# CH32V407WEU-R0.net
KiCad netlist of a schematic drawn in Altium Designer
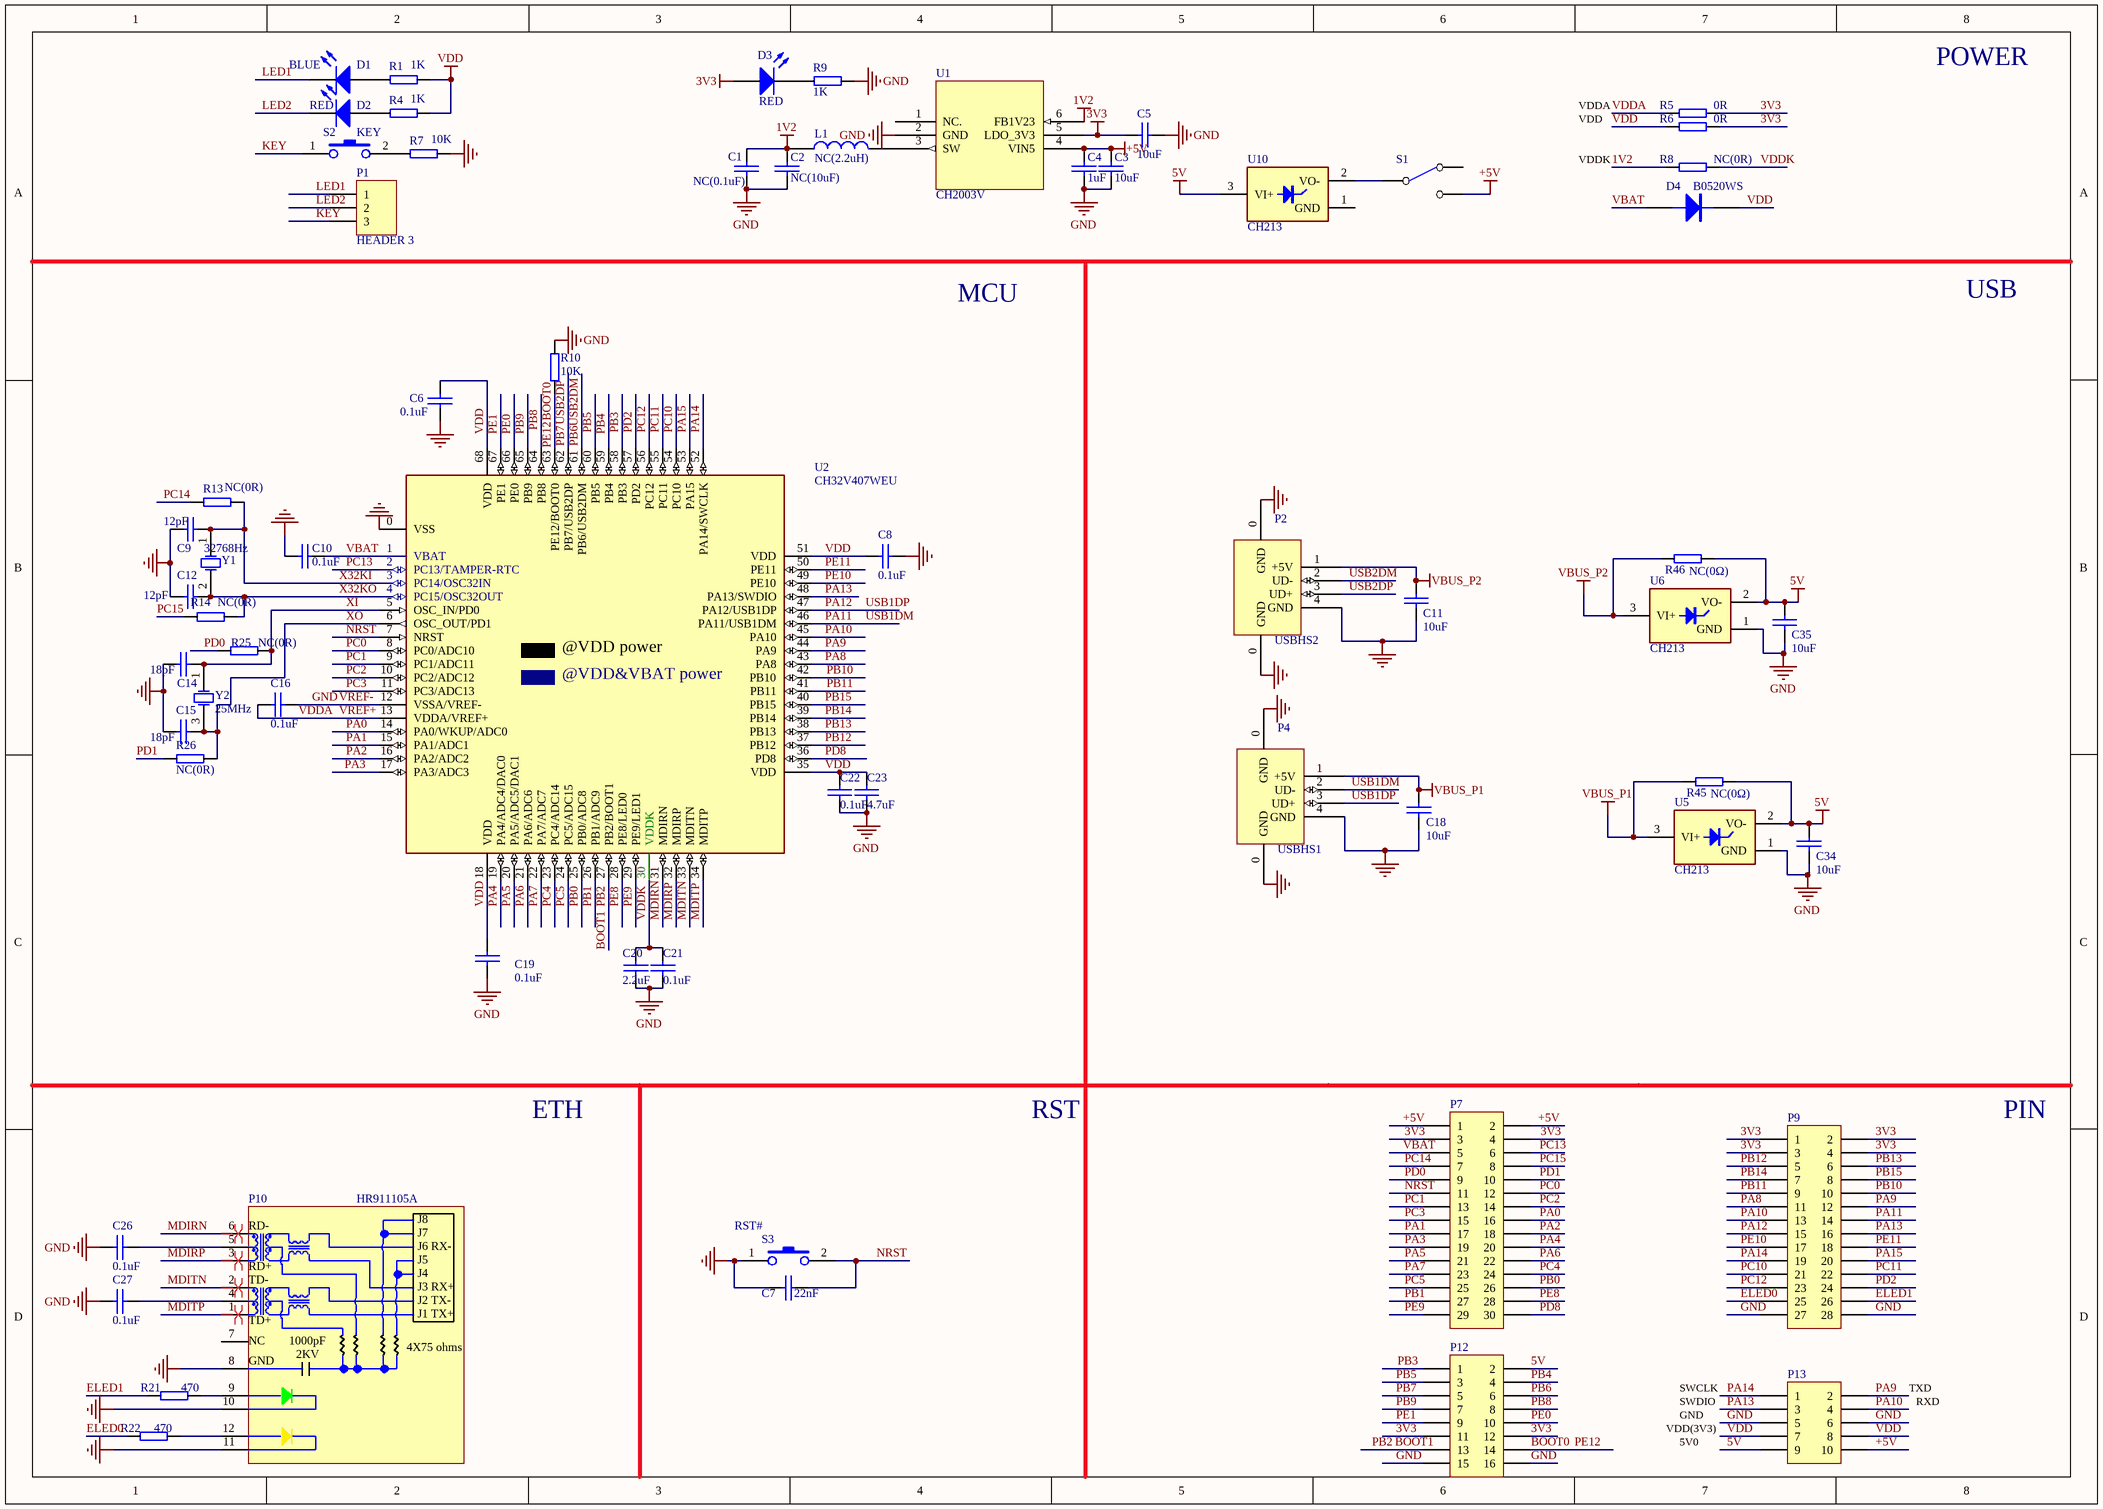
[diagram p0: CH32V407WEU-R0.SchDoc]

(export (version "E")
  (design (tool "Eeschema 10.0.6"))
  (components
    (comp (ref "C1")
      (value "NC(0.1uF)")
      (footprint "0402_C")
      (description "Capacitor")
      (libsource (lib "") (part "CAP_1"))
    )
    (comp (ref "C2")
      (value "NC(10uF)")
      (footprint "0603_C")
      (description "Capacitor")
      (libsource (lib "*") (part "CAP"))
    )
    (comp (ref "C3")
      (value "10uF")
      (footprint "0603_C")
      (description "Capacitor")
      (libsource (lib "*") (part "CAP"))
    )
    (comp (ref "C4")
      (value "1uF")
      (footprint "0402_C")
      (description "Capacitor")
      (libsource (lib "") (part "CAP_1"))
    )
    (comp (ref "C5")
      (value "10uF")
      (footprint "0603_C")
      (description "Capacitor")
      (libsource (lib "*") (part "CAP"))
    )
    (comp (ref "C6")
      (value "0.1uF")
      (footprint "0402_C")
      (description "Capacitor")
      (libsource (lib "*") (part "CAP"))
    )
    (comp (ref "C7")
      (value "22nF")
      (footprint "0402_C")
      (description "Capacitor")
      (libsource (lib "") (part "CAP_2"))
    )
    (comp (ref "C8")
      (value "0.1uF")
      (footprint "0402_C")
      (description "Capacitor")
      (libsource (lib "*") (part "CAP"))
    )
    (comp (ref "C9")
      (value "12pF")
      (footprint "0402_C")
      (description "Capacitor")
      (libsource (lib "*") (part "CAP"))
    )
    (comp (ref "C10")
      (value "0.1uF")
      (footprint "0402_C")
      (description "Capacitor")
      (libsource (lib "*") (part "CAP"))
    )
    (comp (ref "C11")
      (value "10uF")
      (footprint "0603_C")
      (description "Capacitor")
      (libsource (lib "") (part "CAP_2"))
    )
    (comp (ref "C12")
      (value "12pF")
      (footprint "0402_C")
      (description "Capacitor")
      (libsource (lib "*") (part "CAP"))
    )
    (comp (ref "C14")
      (value "18pF")
      (footprint "0402_C")
      (description "Capacitor")
      (libsource (lib "*") (part "CAP"))
    )
    (comp (ref "C15")
      (value "18pF")
      (footprint "0402_C")
      (description "Capacitor")
      (libsource (lib "*") (part "CAP"))
    )
    (comp (ref "C16")
      (value "0.1uF")
      (footprint "0402_C")
      (description "Capacitor")
      (libsource (lib "*") (part "CAP"))
    )
    (comp (ref "C18")
      (value "10uF")
      (footprint "0603_C")
      (description "Capacitor")
      (libsource (lib "") (part "CAP_2"))
    )
    (comp (ref "C19")
      (value "0.1uF")
      (footprint "0402_C")
      (description "Capacitor")
      (libsource (lib "*") (part "CAP"))
    )
    (comp (ref "C20")
      (value "2.2uF")
      (footprint "0402_C")
      (description "Capacitor")
      (libsource (lib "*") (part "CAP"))
    )
    (comp (ref "C21")
      (value "0.1uF")
      (footprint "0402_C")
      (description "Capacitor")
      (libsource (lib "*") (part "CAP"))
    )
    (comp (ref "C22")
      (value "0.1uF")
      (footprint "0402_C")
      (description "Capacitor")
      (libsource (lib "*") (part "CAP"))
    )
    (comp (ref "C23")
      (value "4.7uF")
      (footprint "0402_C")
      (description "Capacitor")
      (libsource (lib "*") (part "CAP"))
    )
    (comp (ref "C26")
      (value "0.1uF")
      (footprint "0402_C")
      (description "Capacitor")
      (libsource (lib "wch_sch_others") (part "CAP"))
    )
    (comp (ref "C27")
      (value "0.1uF")
      (footprint "0402_C")
      (description "Capacitor")
      (libsource (lib "wch_sch_others") (part "CAP"))
    )
    (comp (ref "C34")
      (value "10uF")
      (footprint "0603_C")
      (description "Capacitor")
      (libsource (lib "") (part "CAP_2"))
    )
    (comp (ref "C35")
      (value "10uF")
      (footprint "0603_C")
      (description "Capacitor")
      (libsource (lib "") (part "CAP_2"))
    )
    (comp (ref "D1")
      (value "BLUE")
      (footprint "0603+")
      (description "Typical INFRARED GaAs LED")
      (fields (field (name "PUBLISHER") "Altium Limited"))
      (libsource (lib "*") (part "LED0"))
    )
    (comp (ref "D2")
      (value "RED")
      (footprint "0603+")
      (description "Typical INFRARED GaAs LED")
      (fields (field (name "PUBLISHER") "Altium Limited"))
      (libsource (lib "*") (part "LED0"))
    )
    (comp (ref "D3")
      (value "RED")
      (footprint "0603+")
      (description "Typical INFRARED GaAs LED")
      (fields (field (name "PUBLISHER") "Altium Limited"))
      (libsource (lib "*") (part "LED0"))
    )
    (comp (ref "D4")
      (value "B0520WS")
      (footprint "SOD-323")
      (description "Diode")
      (libsource (lib "*") (part "DIODE"))
    )
    (comp (ref "L1") (value "NC(2.2uH)") (footprint "CD32") (libsource (lib "*") (part "INDUCTOR")))
    (comp (ref "P1")
      (value "HEADER 3")
      (footprint "SIP3-2.54MM")
      (description "Header, 3-Pin")
      (libsource (lib "wch_sch_others") (part "HEADER 3"))
    )
    (comp (ref "P2")
      (value "USBHS2")
      (footprint "USBAF")
      (description "USB Port")
      (libsource (lib "*") (part "USB"))
    )
    (comp (ref "P4")
      (value "USBHS1")
      (footprint "USBAF")
      (description "USB Port")
      (libsource (lib "*") (part "USB"))
    )
    (comp (ref "P7")
      (value "HEADER 15x2")
      (footprint "MYPCB:IDC30-2.54MM")
      (description "Header, 15-Pin, Dual row")
      (libsource (lib "wch_sch_others") (part "HEADER 15x2"))
    )
    (comp (ref "P9")
      (value "HEADER 14x2")
      (footprint "MYPCB:IDC28-2.54MM")
      (description "Header, 14-Pin, Dual row")
      (libsource (lib "wch_sch_others") (part "HEADER 14x2"))
    )
    (comp (ref "P10") (value "HR911105A") (footprint "HR911105A") (libsource (lib "*") (part "HR911105A")))
    (comp (ref "P12")
      (value "Ppin")
      (footprint "IDC16-2.54mm")
      (description "Header, 8-Pin, Dual row, Right Angle")
      (fields (field (name "PUBLISHER") "Altium Limited"))
      (libsource (lib "Miscellaneous Connectors") (part "Header 8X2H"))
    )
    (comp (ref "P13")
      (value "LINK")
      (footprint "IDC10-2.54mm")
      (description "Header, 5-Pin, Dual row, Right Angle")
      (fields (field (name "PUBLISHER") "Altium Limited"))
      (libsource (lib "Miscellaneous Connectors") (part "Header 5X2H"))
    )
    (comp (ref "R1") (value "1K") (footprint "0402") (libsource (lib "wch_sch_others") (part "RES")))
    (comp (ref "R4") (value "1K") (footprint "0402") (libsource (lib "wch_sch_others") (part "RES")))
    (comp (ref "R5") (value "0R") (footprint "0402") (libsource (lib "*") (part "R")))
    (comp (ref "R6") (value "0R") (footprint "0402") (libsource (lib "*") (part "R")))
    (comp (ref "R7") (value "10K") (footprint "0402") (libsource (lib "wch_sch_others") (part "RES")))
    (comp (ref "R8") (value "NC(0R)") (footprint "0402") (libsource (lib "*") (part "R")))
    (comp (ref "R9") (value "1K") (footprint "0402") (libsource (lib "wch_sch_others") (part "RES")))
    (comp (ref "R10") (value "10K") (footprint "0402") (libsource (lib "wch_sch_others") (part "RES")))
    (comp (ref "R13") (value "NC(0R)") (footprint "0402") (libsource (lib "wch_sch_others") (part "RES")))
    (comp (ref "R14") (value "NC(0R)") (footprint "0402") (libsource (lib "wch_sch_others") (part "RES")))
    (comp (ref "R21") (value "470") (footprint "0402") (libsource (lib "wch_sch_others") (part "RES")))
    (comp (ref "R22") (value "470") (footprint "0402") (libsource (lib "wch_sch_others") (part "RES")))
    (comp (ref "R25") (value "NC(0R)") (footprint "0402") (libsource (lib "wch_sch_others") (part "RES")))
    (comp (ref "R26") (value "NC(0R)") (footprint "0402") (libsource (lib "wch_sch_others") (part "RES")))
    (comp (ref "R45") (value "NC(0Ω)") (footprint "0402") (libsource (lib "wch_sch_others") (part "RES")))
    (comp (ref "R46") (value "NC(0Ω)") (footprint "0402") (libsource (lib "wch_sch_others") (part "RES")))
    (comp (ref "S1") (value "SW SPDT") (footprint "SW1") (libsource (lib "*") (part "SW SPDT")))
    (comp (ref "S2")
      (value "KEY")
      (footprint "SMD_6.1x3.65x2.5mm-KEY")
      (libsource (lib "wch_sch_others") (part "KEY1"))
    )
    (comp (ref "S3")
      (value "RST#")
      (footprint "SMD_6.1x3.65x2.5mm-KEY")
      (libsource (lib "wch_sch_others") (part "KEY1"))
    )
    (comp (ref "U1")
      (value "CH2003V")
      (footprint "SOT-23-6")
      (description "Step-Down DC-DC Converter, 5V input, 1.23V * 800mA output, with LDO 3.3V * 200mA")
      (libsource (lib "CHXXX") (part "CH2003V"))
    )
    (comp (ref "U2")
      (value "CH32V407WEU")
      (footprint "QFN68_8X8")
      (description "RISC-V FPU HD-MCU, 175MHz, USB_480M, 100M Ethernet & Phy, CAN, ADC, DAC")
      (libsource (lib "CHXXX") (part "CH32V407WEU"))
    )
    (comp (ref "U5")
      (value "CH213")
      (footprint "SOT-23-3")
      (description "Ideal Diode 5V*1A")
      (libsource (lib "CHXXX") (part "CH213E"))
    )
    (comp (ref "U6")
      (value "CH213")
      (footprint "SOT-23-3")
      (description "Ideal Diode 5V*1A")
      (libsource (lib "CHXXX") (part "CH213E"))
    )
    (comp (ref "U10")
      (value "CH213")
      (footprint "SOT-23-3")
      (description "Ideal Diode 5V*1A")
      (libsource (lib "CHXXX") (part "CH213E"))
    )
    (comp (ref "Y1")
      (value "32768Hz")
      (footprint "FC-135")
      (description "Crystal Oscillator")
      (fields (field (name "PUBLISHER") "Altium Limited"))
      (libsource (lib "*") (part "XTAL"))
    )
    (comp (ref "Y2")
      (value "25MHz")
      (footprint "XT3225")
      (description "Crystal Oscillator")
      (fields (field (name "PUBLISHER") "Altium Limited"))
      (libsource (lib "") (part "XTAL_1"))
    )
  )
  (nets
    (net (code "1") (name "+5V") (class "Default")
      (node (ref "C3") (pin "2") (pinfunction "2_2") (pintype "passive"))
      (node (ref "C4") (pin "2") (pinfunction "2_2") (pintype "passive"))
      (node (ref "P13") (pin "10") (pinfunction "10_10") (pintype "passive"))
      (node (ref "P7") (pin "1") (pinfunction "1_1") (pintype "passive"))
      (node (ref "P7") (pin "2") (pinfunction "2_2") (pintype "passive"))
      (node (ref "S1") (pin "2") (pinfunction "NC_2") (pintype "passive"))
      (node (ref "U1") (pin "4") (pinfunction "VIN5_4") (pintype "power_in"))
    )
    (net (code "3") (name "/BOOT0") (class "Default")
      (node (ref "P12") (pin "14") (pinfunction "14_14") (pintype "passive"))
      (node (ref "R10") (pin "2") (pintype "passive"))
      (node (ref "U2") (pin "63") (pinfunction "PE12/BOOT0_63") (pintype "bidirectional"))
    )
    (net (code "4") (name "/BOOT1") (class "Default")
      (node (ref "P12") (pin "13") (pinfunction "13_13") (pintype "passive"))
      (node (ref "U2") (pin "27") (pinfunction "PB2/BOOT1_27") (pintype "bidirectional"))
    )
    (net (code "5") (name "/ELED0") (class "Default")
      (node (ref "P9") (pin "25") (pinfunction "25_25") (pintype "passive"))
      (node (ref "R22") (pin "1") (pintype "passive"))
    )
    (net (code "6") (name "/ELED1") (class "Default")
      (node (ref "P9") (pin "26") (pinfunction "26_26") (pintype "passive"))
      (node (ref "R21") (pin "1") (pintype "passive"))
    )
    (net (code "7") (name "/KEY") (class "Default")
      (node (ref "P1") (pin "3") (pinfunction "3_3") (pintype "passive"))
      (node (ref "S2") (pin "1") (pinfunction "1_1") (pintype "passive"))
    )
    (net (code "8") (name "/LED1") (class "Default")
      (node (ref "D1") (pin "2") (pinfunction "K_2") (pintype "passive"))
      (node (ref "P1") (pin "1") (pinfunction "1_1") (pintype "passive"))
    )
    (net (code "9") (name "/LED2") (class "Default")
      (node (ref "D2") (pin "2") (pinfunction "K_2") (pintype "passive"))
      (node (ref "P1") (pin "2") (pinfunction "2_2") (pintype "passive"))
    )
    (net (code "10") (name "/MDIRN") (class "Default")
      (node (ref "P10") (pin "6") (pintype "passive"))
      (node (ref "U2") (pin "31") (pinfunction "MDIRN_31") (pintype "bidirectional"))
    )
    (net (code "11") (name "/MDIRP") (class "Default")
      (node (ref "P10") (pin "3") (pintype "passive"))
      (node (ref "U2") (pin "32") (pinfunction "MDIRP_32") (pintype "bidirectional"))
    )
    (net (code "12") (name "/MDITN") (class "Default")
      (node (ref "P10") (pin "2") (pintype "passive"))
      (node (ref "U2") (pin "33") (pinfunction "MDITN_33") (pintype "bidirectional"))
    )
    (net (code "13") (name "/MDITP") (class "Default")
      (node (ref "P10") (pin "1") (pintype "passive"))
      (node (ref "U2") (pin "34") (pinfunction "MDITP_34") (pintype "bidirectional"))
    )
    (net (code "14") (name "/NRST") (class "Default")
      (node (ref "C7") (pin "2") (pinfunction "2_2") (pintype "passive"))
      (node (ref "P7") (pin "11") (pinfunction "11_11") (pintype "passive"))
      (node (ref "S3") (pin "2") (pinfunction "2_2") (pintype "passive"))
      (node (ref "U2") (pin "7") (pinfunction "NRST_7") (pintype "input"))
    )
    (net (code "15") (name "/PA0") (class "Default")
      (node (ref "P7") (pin "16") (pinfunction "16_16") (pintype "passive"))
      (node (ref "U2") (pin "14") (pinfunction "PA0/WKUP/ADC0_14") (pintype "bidirectional"))
    )
    (net (code "16") (name "/PA1") (class "Default")
      (node (ref "P7") (pin "17") (pinfunction "17_17") (pintype "passive"))
      (node (ref "U2") (pin "15") (pinfunction "PA1/ADC1_15") (pintype "bidirectional"))
    )
    (net (code "17") (name "/PA2") (class "Default")
      (node (ref "P7") (pin "18") (pinfunction "18_18") (pintype "passive"))
      (node (ref "U2") (pin "16") (pinfunction "PA2/ADC2_16") (pintype "bidirectional"))
    )
    (net (code "18") (name "/PA3") (class "Default")
      (node (ref "P7") (pin "19") (pinfunction "19_19") (pintype "passive"))
      (node (ref "U2") (pin "17") (pinfunction "PA3/ADC3_17") (pintype "bidirectional"))
    )
    (net (code "19") (name "/PA4") (class "Default")
      (node (ref "P7") (pin "20") (pinfunction "20_20") (pintype "passive"))
      (node (ref "U2") (pin "19") (pinfunction "PA4/ADC4/DAC0_19") (pintype "bidirectional"))
    )
    (net (code "20") (name "/PA5") (class "Default")
      (node (ref "P7") (pin "21") (pinfunction "21_21") (pintype "passive"))
      (node (ref "U2") (pin "20") (pinfunction "PA5/ADC5/DAC1_20") (pintype "bidirectional"))
    )
    (net (code "21") (name "/PA6") (class "Default")
      (node (ref "P7") (pin "22") (pinfunction "22_22") (pintype "passive"))
      (node (ref "U2") (pin "21") (pinfunction "PA6/ADC6_21") (pintype "bidirectional"))
    )
    (net (code "22") (name "/PA7") (class "Default")
      (node (ref "P7") (pin "23") (pinfunction "23_23") (pintype "passive"))
      (node (ref "U2") (pin "22") (pinfunction "PA7/ADC7_22") (pintype "bidirectional"))
    )
    (net (code "23") (name "/PA8") (class "Default")
      (node (ref "P9") (pin "11") (pinfunction "11_11") (pintype "passive"))
      (node (ref "U2") (pin "43") (pinfunction "PA8_43") (pintype "bidirectional"))
    )
    (net (code "24") (name "/PA9") (class "Default")
      (node (ref "P13") (pin "2") (pinfunction "2_2") (pintype "passive"))
      (node (ref "P9") (pin "12") (pinfunction "12_12") (pintype "passive"))
      (node (ref "U2") (pin "44") (pinfunction "PA9_44") (pintype "bidirectional"))
    )
    (net (code "25") (name "/PA10") (class "Default")
      (node (ref "P13") (pin "4") (pinfunction "4_4") (pintype "passive"))
      (node (ref "P9") (pin "13") (pinfunction "13_13") (pintype "passive"))
      (node (ref "U2") (pin "45") (pinfunction "PA10_45") (pintype "bidirectional"))
    )
    (net (code "26") (name "/PA11") (class "Default")
      (node (ref "P4") (pin "2") (pinfunction "UD-_2") (pintype "bidirectional"))
      (node (ref "P9") (pin "14") (pinfunction "14_14") (pintype "passive"))
      (node (ref "U2") (pin "46") (pinfunction "PA11/USB1DM_46") (pintype "bidirectional"))
    )
    (net (code "27") (name "/PA12") (class "Default")
      (node (ref "P4") (pin "3") (pinfunction "UD+_3") (pintype "bidirectional"))
      (node (ref "P9") (pin "15") (pinfunction "15_15") (pintype "passive"))
      (node (ref "U2") (pin "47") (pinfunction "PA12/USB1DP_47") (pintype "bidirectional"))
    )
    (net (code "28") (name "/PA13") (class "Default")
      (node (ref "P13") (pin "3") (pinfunction "3_3") (pintype "passive"))
      (node (ref "P9") (pin "16") (pinfunction "16_16") (pintype "passive"))
      (node (ref "U2") (pin "48") (pinfunction "PA13/SWDIO_48") (pintype "bidirectional"))
    )
    (net (code "29") (name "/PA14") (class "Default")
      (node (ref "P13") (pin "1") (pinfunction "1_1") (pintype "passive"))
      (node (ref "P9") (pin "19") (pinfunction "19_19") (pintype "passive"))
      (node (ref "U2") (pin "52") (pinfunction "PA14/SWCLK_52") (pintype "bidirectional"))
    )
    (net (code "30") (name "/PA15") (class "Default")
      (node (ref "P9") (pin "20") (pinfunction "20_20") (pintype "passive"))
      (node (ref "U2") (pin "53") (pinfunction "PA15_53") (pintype "bidirectional"))
    )
    (net (code "31") (name "/PB0") (class "Default")
      (node (ref "P7") (pin "26") (pinfunction "26_26") (pintype "passive"))
      (node (ref "U2") (pin "25") (pinfunction "PB0/ADC8_25") (pintype "bidirectional"))
    )
    (net (code "32") (name "/PB1") (class "Default")
      (node (ref "P7") (pin "27") (pinfunction "27_27") (pintype "passive"))
      (node (ref "U2") (pin "26") (pinfunction "PB1/ADC9_26") (pintype "bidirectional"))
    )
    (net (code "33") (name "/PB3") (class "Default")
      (node (ref "P12") (pin "1") (pinfunction "1_1") (pintype "passive"))
      (node (ref "U2") (pin "58") (pinfunction "PB3_58") (pintype "bidirectional"))
    )
    (net (code "34") (name "/PB4") (class "Default")
      (node (ref "P12") (pin "4") (pinfunction "4_4") (pintype "passive"))
      (node (ref "U2") (pin "59") (pinfunction "PB4_59") (pintype "bidirectional"))
    )
    (net (code "35") (name "/PB5") (class "Default")
      (node (ref "P12") (pin "3") (pinfunction "3_3") (pintype "passive"))
      (node (ref "U2") (pin "60") (pinfunction "PB5_60") (pintype "bidirectional"))
    )
    (net (code "36") (name "/PB6") (class "Default")
      (node (ref "P12") (pin "6") (pinfunction "6_6") (pintype "passive"))
      (node (ref "P2") (pin "2") (pinfunction "UD-_2") (pintype "bidirectional"))
      (node (ref "U2") (pin "61") (pinfunction "PB6/USB2DM_61") (pintype "bidirectional"))
    )
    (net (code "37") (name "/PB7") (class "Default")
      (node (ref "P12") (pin "5") (pinfunction "5_5") (pintype "passive"))
      (node (ref "P2") (pin "3") (pinfunction "UD+_3") (pintype "bidirectional"))
      (node (ref "U2") (pin "62") (pinfunction "PB7/USB2DP_62") (pintype "bidirectional"))
    )
    (net (code "38") (name "/PB8") (class "Default")
      (node (ref "P12") (pin "8") (pinfunction "8_8") (pintype "passive"))
      (node (ref "U2") (pin "64") (pinfunction "PB8_64") (pintype "bidirectional"))
    )
    (net (code "39") (name "/PB9") (class "Default")
      (node (ref "P12") (pin "7") (pinfunction "7_7") (pintype "passive"))
      (node (ref "U2") (pin "65") (pinfunction "PB9_65") (pintype "bidirectional"))
    )
    (net (code "40") (name "/PB10") (class "Default")
      (node (ref "P9") (pin "10") (pinfunction "10_10") (pintype "passive"))
      (node (ref "U2") (pin "42") (pinfunction "PB10_42") (pintype "bidirectional"))
    )
    (net (code "41") (name "/PB11") (class "Default")
      (node (ref "P9") (pin "9") (pinfunction "9_9") (pintype "passive"))
      (node (ref "U2") (pin "41") (pinfunction "PB11_41") (pintype "bidirectional"))
    )
    (net (code "42") (name "/PB12") (class "Default")
      (node (ref "P9") (pin "5") (pinfunction "5_5") (pintype "passive"))
      (node (ref "U2") (pin "37") (pinfunction "PB12_37") (pintype "bidirectional"))
    )
    (net (code "43") (name "/PB13") (class "Default")
      (node (ref "P9") (pin "6") (pinfunction "6_6") (pintype "passive"))
      (node (ref "U2") (pin "38") (pinfunction "PB13_38") (pintype "bidirectional"))
    )
    (net (code "44") (name "/PB14") (class "Default")
      (node (ref "P9") (pin "7") (pinfunction "7_7") (pintype "passive"))
      (node (ref "U2") (pin "39") (pinfunction "PB14_39") (pintype "bidirectional"))
    )
    (net (code "45") (name "/PB15") (class "Default")
      (node (ref "P9") (pin "8") (pinfunction "8_8") (pintype "passive"))
      (node (ref "U2") (pin "40") (pinfunction "PB15_40") (pintype "bidirectional"))
    )
    (net (code "46") (name "/PC0") (class "Default")
      (node (ref "P7") (pin "12") (pinfunction "12_12") (pintype "passive"))
      (node (ref "U2") (pin "8") (pinfunction "PC0/ADC10_8") (pintype "bidirectional"))
    )
    (net (code "47") (name "/PC1") (class "Default")
      (node (ref "P7") (pin "13") (pinfunction "13_13") (pintype "passive"))
      (node (ref "U2") (pin "9") (pinfunction "PC1/ADC11_9") (pintype "bidirectional"))
    )
    (net (code "48") (name "/PC2") (class "Default")
      (node (ref "P7") (pin "14") (pinfunction "14_14") (pintype "passive"))
      (node (ref "U2") (pin "10") (pinfunction "PC2/ADC12_10") (pintype "bidirectional"))
    )
    (net (code "49") (name "/PC3") (class "Default")
      (node (ref "P7") (pin "15") (pinfunction "15_15") (pintype "passive"))
      (node (ref "U2") (pin "11") (pinfunction "PC3/ADC13_11") (pintype "bidirectional"))
    )
    (net (code "50") (name "/PC4") (class "Default")
      (node (ref "P7") (pin "24") (pinfunction "24_24") (pintype "passive"))
      (node (ref "U2") (pin "23") (pinfunction "PC4/ADC14_23") (pintype "bidirectional"))
    )
    (net (code "51") (name "/PC5") (class "Default")
      (node (ref "P7") (pin "25") (pinfunction "25_25") (pintype "passive"))
      (node (ref "U2") (pin "24") (pinfunction "PC5/ADC15_24") (pintype "bidirectional"))
    )
    (net (code "52") (name "/PC10") (class "Default")
      (node (ref "P9") (pin "21") (pinfunction "21_21") (pintype "passive"))
      (node (ref "U2") (pin "54") (pinfunction "PC10_54") (pintype "bidirectional"))
    )
    (net (code "53") (name "/PC11") (class "Default")
      (node (ref "P9") (pin "22") (pinfunction "22_22") (pintype "passive"))
      (node (ref "U2") (pin "55") (pinfunction "PC11_55") (pintype "bidirectional"))
    )
    (net (code "54") (name "/PC12") (class "Default")
      (node (ref "P9") (pin "23") (pinfunction "23_23") (pintype "passive"))
      (node (ref "U2") (pin "56") (pinfunction "PC12_56") (pintype "bidirectional"))
    )
    (net (code "55") (name "/PC13") (class "Default")
      (node (ref "P7") (pin "6") (pinfunction "6_6") (pintype "passive"))
      (node (ref "U2") (pin "2") (pinfunction "PC13/TAMPER-RTC_2") (pintype "bidirectional"))
    )
    (net (code "56") (name "/PC14") (class "Default")
      (node (ref "P7") (pin "7") (pinfunction "7_7") (pintype "passive"))
      (node (ref "R13") (pin "1") (pintype "passive"))
    )
    (net (code "57") (name "/PC15") (class "Default")
      (node (ref "P7") (pin "8") (pinfunction "8_8") (pintype "passive"))
      (node (ref "R14") (pin "1") (pintype "passive"))
    )
    (net (code "58") (name "/PD0") (class "Default")
      (node (ref "P7") (pin "9") (pinfunction "9_9") (pintype "passive"))
      (node (ref "R25") (pin "1") (pintype "passive"))
    )
    (net (code "59") (name "/PD1") (class "Default")
      (node (ref "P7") (pin "10") (pinfunction "10_10") (pintype "passive"))
      (node (ref "R26") (pin "2") (pintype "passive"))
    )
    (net (code "60") (name "/PD2") (class "Default")
      (node (ref "P9") (pin "24") (pinfunction "24_24") (pintype "passive"))
      (node (ref "U2") (pin "57") (pinfunction "PD2_57") (pintype "bidirectional"))
    )
    (net (code "61") (name "/PD8") (class "Default")
      (node (ref "P7") (pin "30") (pinfunction "30_30") (pintype "passive"))
      (node (ref "U2") (pin "36") (pinfunction "PD8_36") (pintype "bidirectional"))
    )
    (net (code "62") (name "/PE0") (class "Default")
      (node (ref "P12") (pin "10") (pinfunction "10_10") (pintype "passive"))
      (node (ref "U2") (pin "66") (pinfunction "PE0_66") (pintype "bidirectional"))
    )
    (net (code "63") (name "/PE1") (class "Default")
      (node (ref "P12") (pin "9") (pinfunction "9_9") (pintype "passive"))
      (node (ref "U2") (pin "67") (pinfunction "PE1_67") (pintype "bidirectional"))
    )
    (net (code "64") (name "/PE8") (class "Default")
      (node (ref "P7") (pin "28") (pinfunction "28_28") (pintype "passive"))
      (node (ref "U2") (pin "28") (pinfunction "PE8/LED0_28") (pintype "bidirectional"))
    )
    (net (code "65") (name "/PE9") (class "Default")
      (node (ref "P7") (pin "29") (pinfunction "29_29") (pintype "passive"))
      (node (ref "U2") (pin "29") (pinfunction "PE9/LED1_29") (pintype "bidirectional"))
    )
    (net (code "66") (name "/PE10") (class "Default")
      (node (ref "P9") (pin "17") (pinfunction "17_17") (pintype "passive"))
      (node (ref "U2") (pin "49") (pinfunction "PE10_49") (pintype "bidirectional"))
    )
    (net (code "67") (name "/PE11") (class "Default")
      (node (ref "P9") (pin "18") (pinfunction "18_18") (pintype "passive"))
      (node (ref "U2") (pin "50") (pinfunction "PE11_50") (pintype "bidirectional"))
    )
    (net (code "68") (name "/VBAT") (class "Default")
      (node (ref "C10") (pin "2") (pinfunction "2_2") (pintype "passive"))
      (node (ref "D4") (pin "1") (pinfunction "A_1") (pintype "passive"))
      (node (ref "P7") (pin "5") (pinfunction "5_5") (pintype "passive"))
      (node (ref "U2") (pin "1") (pinfunction "VBAT_1") (pintype "power_in"))
    )
    (net (code "69") (name "/VDDA") (class "Default")
      (node (ref "C16") (pin "1") (pinfunction "1_1") (pintype "passive"))
      (node (ref "R5") (pin "2") (pinfunction "2_2") (pintype "passive"))
      (node (ref "U2") (pin "13") (pinfunction "VDDA/VREF+_13") (pintype "power_in"))
    )
    (net (code "70") (name "/VDDK") (class "Default")
      (node (ref "C20") (pin "2") (pinfunction "2_2") (pintype "passive"))
      (node (ref "C21") (pin "2") (pinfunction "2_2") (pintype "passive"))
      (node (ref "R8") (pin "1") (pinfunction "1_1") (pintype "passive"))
      (node (ref "U2") (pin "30") (pinfunction "VDDK_30") (pintype "power_in"))
    )
    (net (code "71") (name "/X32KI") (class "Default")
      (node (ref "C9") (pin "2") (pinfunction "2_2") (pintype "passive"))
      (node (ref "R13") (pin "2") (pintype "passive"))
      (node (ref "U2") (pin "3") (pinfunction "PC14/OSC32IN_3") (pintype "bidirectional"))
      (node (ref "Y1") (pin "1") (pinfunction "OSC1_1") (pintype "passive"))
    )
    (net (code "72") (name "/X32KO") (class "Default")
      (node (ref "C12") (pin "2") (pinfunction "2_2") (pintype "passive"))
      (node (ref "R14") (pin "2") (pintype "passive"))
      (node (ref "U2") (pin "4") (pinfunction "PC15/OSC32OUT_4") (pintype "bidirectional"))
      (node (ref "Y1") (pin "2") (pinfunction "OSC2_2") (pintype "passive"))
    )
    (net (code "73") (name "/XI") (class "Default")
      (node (ref "C14") (pin "2") (pinfunction "2_2") (pintype "passive"))
      (node (ref "R25") (pin "2") (pintype "passive"))
      (node (ref "U2") (pin "5") (pinfunction "OSC_IN/PD0_5") (pintype "input"))
      (node (ref "Y2") (pin "1") (pinfunction "OSC1_1") (pintype "passive"))
    )
    (net (code "74") (name "/XO") (class "Default")
      (node (ref "C15") (pin "2") (pinfunction "2_2") (pintype "passive"))
      (node (ref "R26") (pin "1") (pintype "passive"))
      (node (ref "U2") (pin "6") (pinfunction "OSC_OUT/PD1_6") (pintype "output"))
      (node (ref "Y2") (pin "3") (pinfunction "OSC2_3") (pintype "passive"))
    )
    (net (code "75") (name "1V2") (class "Default")
      (node (ref "C1") (pin "2") (pinfunction "2_2") (pintype "passive"))
      (node (ref "C2") (pin "2") (pinfunction "2_2") (pintype "passive"))
      (node (ref "L1") (pin "2") (pinfunction "2_2") (pintype "passive"))
      (node (ref "R8") (pin "2") (pinfunction "2_2") (pintype "passive"))
      (node (ref "U1") (pin "6") (pinfunction "FB1V23_6") (pintype "input"))
    )
    (net (code "76") (name "3V3") (class "Default")
      (node (ref "C5") (pin "2") (pinfunction "2_2") (pintype "passive"))
      (node (ref "D3") (pin "1") (pinfunction "A_1") (pintype "passive"))
      (node (ref "P12") (pin "11") (pinfunction "11_11") (pintype "passive"))
      (node (ref "P12") (pin "12") (pinfunction "12_12") (pintype "passive"))
      (node (ref "P7") (pin "3") (pinfunction "3_3") (pintype "passive"))
      (node (ref "P7") (pin "4") (pinfunction "4_4") (pintype "passive"))
      (node (ref "P9") (pin "1") (pinfunction "1_1") (pintype "passive"))
      (node (ref "P9") (pin "2") (pinfunction "2_2") (pintype "passive"))
      (node (ref "P9") (pin "3") (pinfunction "3_3") (pintype "passive"))
      (node (ref "P9") (pin "4") (pinfunction "4_4") (pintype "passive"))
      (node (ref "R5") (pin "1") (pinfunction "1_1") (pintype "passive"))
      (node (ref "R6") (pin "1") (pinfunction "1_1") (pintype "passive"))
      (node (ref "U1") (pin "5") (pinfunction "LDO_3V3_5") (pintype "power_in"))
    )
    (net (code "77") (name "5V") (class "Default")
      (node (ref "C34") (pin "1") (pinfunction "1_1") (pintype "passive"))
      (node (ref "C35") (pin "1") (pinfunction "1_1") (pintype "passive"))
      (node (ref "P12") (pin "2") (pinfunction "2_2") (pintype "passive"))
      (node (ref "P13") (pin "9") (pinfunction "9_9") (pintype "passive"))
      (node (ref "R45") (pin "1") (pintype "passive"))
      (node (ref "R46") (pin "1") (pintype "passive"))
      (node (ref "U10") (pin "3") (pinfunction "VI+_3") (pintype "power_in"))
      (node (ref "U5") (pin "2") (pinfunction "VO-_2") (pintype "power_in"))
      (node (ref "U6") (pin "2") (pinfunction "VO-_2") (pintype "power_in"))
    )
    (net (code "78") (name "GND") (class "Default")
      (node (ref "C1") (pin "1") (pinfunction "1_1") (pintype "passive"))
      (node (ref "C10") (pin "1") (pinfunction "1_1") (pintype "passive"))
      (node (ref "C11") (pin "2") (pinfunction "2_2") (pintype "passive"))
      (node (ref "C12") (pin "1") (pinfunction "1_1") (pintype "passive"))
      (node (ref "C14") (pin "1") (pinfunction "1_1") (pintype "passive"))
      (node (ref "C15") (pin "1") (pinfunction "1_1") (pintype "passive"))
      (node (ref "C16") (pin "2") (pinfunction "2_2") (pintype "passive"))
      (node (ref "C18") (pin "2") (pinfunction "2_2") (pintype "passive"))
      (node (ref "C19") (pin "1") (pinfunction "1_1") (pintype "passive"))
      (node (ref "C2") (pin "1") (pinfunction "1_1") (pintype "passive"))
      (node (ref "C20") (pin "1") (pinfunction "1_1") (pintype "passive"))
      (node (ref "C21") (pin "1") (pinfunction "1_1") (pintype "passive"))
      (node (ref "C22") (pin "1") (pinfunction "1_1") (pintype "passive"))
      (node (ref "C23") (pin "1") (pinfunction "1_1") (pintype "passive"))
      (node (ref "C26") (pin "1") (pinfunction "1_1") (pintype "passive"))
      (node (ref "C27") (pin "1") (pinfunction "1_1") (pintype "passive"))
      (node (ref "C3") (pin "1") (pinfunction "1_1") (pintype "passive"))
      (node (ref "C34") (pin "2") (pinfunction "2_2") (pintype "passive"))
      (node (ref "C35") (pin "2") (pinfunction "2_2") (pintype "passive"))
      (node (ref "C4") (pin "1") (pinfunction "1_1") (pintype "passive"))
      (node (ref "C5") (pin "1") (pinfunction "1_1") (pintype "passive"))
      (node (ref "C6") (pin "1") (pinfunction "1_1") (pintype "passive"))
      (node (ref "C7") (pin "1") (pinfunction "1_1") (pintype "passive"))
      (node (ref "C8") (pin "2") (pinfunction "2_2") (pintype "passive"))
      (node (ref "C9") (pin "1") (pinfunction "1_1") (pintype "passive"))
      (node (ref "P10") (pin "10") (pintype "passive"))
      (node (ref "P10") (pin "11") (pintype "passive"))
      (node (ref "P10") (pin "8") (pintype "passive"))
      (node (ref "P12") (pin "15") (pinfunction "15_15") (pintype "passive"))
      (node (ref "P12") (pin "16") (pinfunction "16_16") (pintype "passive"))
      (node (ref "P13") (pin "5") (pinfunction "5_5") (pintype "passive"))
      (node (ref "P13") (pin "6") (pinfunction "6_6") (pintype "passive"))
      (node (ref "P2") (pin "0") (pinfunction "GND_0") (pintype "power_in"))
      (node (ref "P2") (pin "4") (pinfunction "GND_4") (pintype "power_in"))
      (node (ref "P4") (pin "0") (pinfunction "GND_0") (pintype "power_in"))
      (node (ref "P4") (pin "4") (pinfunction "GND_4") (pintype "power_in"))
      (node (ref "P9") (pin "27") (pinfunction "27_27") (pintype "passive"))
      (node (ref "P9") (pin "28") (pinfunction "28_28") (pintype "passive"))
      (node (ref "R10") (pin "1") (pintype "passive"))
      (node (ref "R7") (pin "1") (pintype "passive"))
      (node (ref "R9") (pin "2") (pintype "passive"))
      (node (ref "S3") (pin "1") (pinfunction "1_1") (pintype "passive"))
      (node (ref "U1") (pin "2") (pinfunction "GND_2") (pintype "power_in"))
      (node (ref "U2") (pin "0") (pinfunction "VSS_0") (pintype "power_in"))
      (node (ref "U2") (pin "12") (pinfunction "VSSA/VREF-_12") (pintype "power_in"))
      (node (ref "U5") (pin "1") (pinfunction "GND_1") (pintype "power_in"))
      (node (ref "U6") (pin "1") (pinfunction "GND_1") (pintype "power_in"))
    )
    (net (code "79") (name "Net-(C26-Pad2)") (class "Default")
      (node (ref "C26") (pin "2") (pinfunction "2_2") (pintype "passive"))
      (node (ref "P10") (pin "5") (pintype "passive"))
    )
    (net (code "80") (name "Net-(C27-Pad2)") (class "Default")
      (node (ref "C27") (pin "2") (pinfunction "2_2") (pintype "passive"))
      (node (ref "P10") (pin "4") (pintype "passive"))
    )
    (net (code "81") (name "Net-(D1-A)") (class "Default")
      (node (ref "D1") (pin "1") (pinfunction "A_1") (pintype "passive"))
      (node (ref "R1") (pin "2") (pintype "passive"))
    )
    (net (code "82") (name "Net-(D2-A)") (class "Default")
      (node (ref "D2") (pin "1") (pinfunction "A_1") (pintype "passive"))
      (node (ref "R4") (pin "2") (pintype "passive"))
    )
    (net (code "83") (name "Net-(D3-K)") (class "Default")
      (node (ref "D3") (pin "2") (pinfunction "K_2") (pintype "passive"))
      (node (ref "R9") (pin "1") (pintype "passive"))
    )
    (net (code "84") (name "Net-(P10-Pad9)") (class "Default")
      (node (ref "P10") (pin "9") (pintype "passive"))
      (node (ref "R21") (pin "2") (pintype "passive"))
    )
    (net (code "85") (name "Net-(P10-Pad12)") (class "Default")
      (node (ref "P10") (pin "12") (pintype "passive"))
      (node (ref "R22") (pin "2") (pintype "passive"))
    )
    (net (code "86") (name "Net-(R7-Pad2)") (class "Default")
      (node (ref "R7") (pin "2") (pintype "passive"))
      (node (ref "S2") (pin "2") (pinfunction "2_2") (pintype "passive"))
    )
    (net (code "87") (name "Net-(S1-COMMON)") (class "Default")
      (node (ref "S1") (pin "1") (pinfunction "COMMON_1") (pintype "passive"))
      (node (ref "U10") (pin "2") (pinfunction "VO-_2") (pintype "power_in"))
    )
    (net (code "88") (name "Net-(U1-SW)") (class "Default")
      (node (ref "L1") (pin "1") (pinfunction "1_1") (pintype "passive"))
      (node (ref "U1") (pin "3") (pinfunction "SW_3") (pintype "output"))
    )
    (net (code "89") (name "VBUS_P1") (class "Default")
      (node (ref "C18") (pin "1") (pinfunction "1_1") (pintype "passive"))
      (node (ref "P4") (pin "1") (pinfunction "+5V_1") (pintype "power_in"))
      (node (ref "R45") (pin "2") (pintype "passive"))
      (node (ref "U5") (pin "3") (pinfunction "VI+_3") (pintype "power_in"))
    )
    (net (code "90") (name "VBUS_P2") (class "Default")
      (node (ref "C11") (pin "1") (pinfunction "1_1") (pintype "passive"))
      (node (ref "P2") (pin "1") (pinfunction "+5V_1") (pintype "power_in"))
      (node (ref "R46") (pin "2") (pintype "passive"))
      (node (ref "U6") (pin "3") (pinfunction "VI+_3") (pintype "power_in"))
    )
    (net (code "91") (name "VDD") (class "Default")
      (node (ref "C19") (pin "2") (pinfunction "2_2") (pintype "passive"))
      (node (ref "C22") (pin "2") (pinfunction "2_2") (pintype "passive"))
      (node (ref "C23") (pin "2") (pinfunction "2_2") (pintype "passive"))
      (node (ref "C6") (pin "2") (pinfunction "2_2") (pintype "passive"))
      (node (ref "C8") (pin "1") (pinfunction "1_1") (pintype "passive"))
      (node (ref "D4") (pin "2") (pinfunction "K_2") (pintype "passive"))
      (node (ref "P13") (pin "7") (pinfunction "7_7") (pintype "passive"))
      (node (ref "P13") (pin "8") (pinfunction "8_8") (pintype "passive"))
      (node (ref "R1") (pin "1") (pintype "passive"))
      (node (ref "R4") (pin "1") (pintype "passive"))
      (node (ref "R6") (pin "2") (pinfunction "2_2") (pintype "passive"))
      (node (ref "U2") (pin "18") (pinfunction "VDD_18") (pintype "power_in"))
      (node (ref "U2") (pin "35") (pinfunction "VDD_35") (pintype "power_in"))
      (node (ref "U2") (pin "51") (pinfunction "VDD_51") (pintype "power_in"))
      (node (ref "U2") (pin "68") (pinfunction "VDD_68") (pintype "power_in"))
    )
    (net (code "92") (name "unconnected-(P10-Pad7)") (class "Default")
      (node (ref "P10") (pin "7") (pintype "passive"))
    )
    (net (code "93") (name "unconnected-(S1-NO-Pad3)") (class "Default")
      (node (ref "S1") (pin "3") (pinfunction "NO_3") (pintype "passive"))
    )
    (net (code "94") (name "unconnected-(U1-NC.-Pad1)") (class "Default")
      (node (ref "U1") (pin "1") (pinfunction "NC._1") (pintype "passive"))
    )
    (net (code "95") (name "unconnected-(U10-GND-Pad1)") (class "Default")
      (node (ref "U10") (pin "1") (pinfunction "GND_1") (pintype "power_in"))
    )
  )
)
